# Schematic_Rev3.net
KiCad netlist of a schematic drawn in Altium Designer
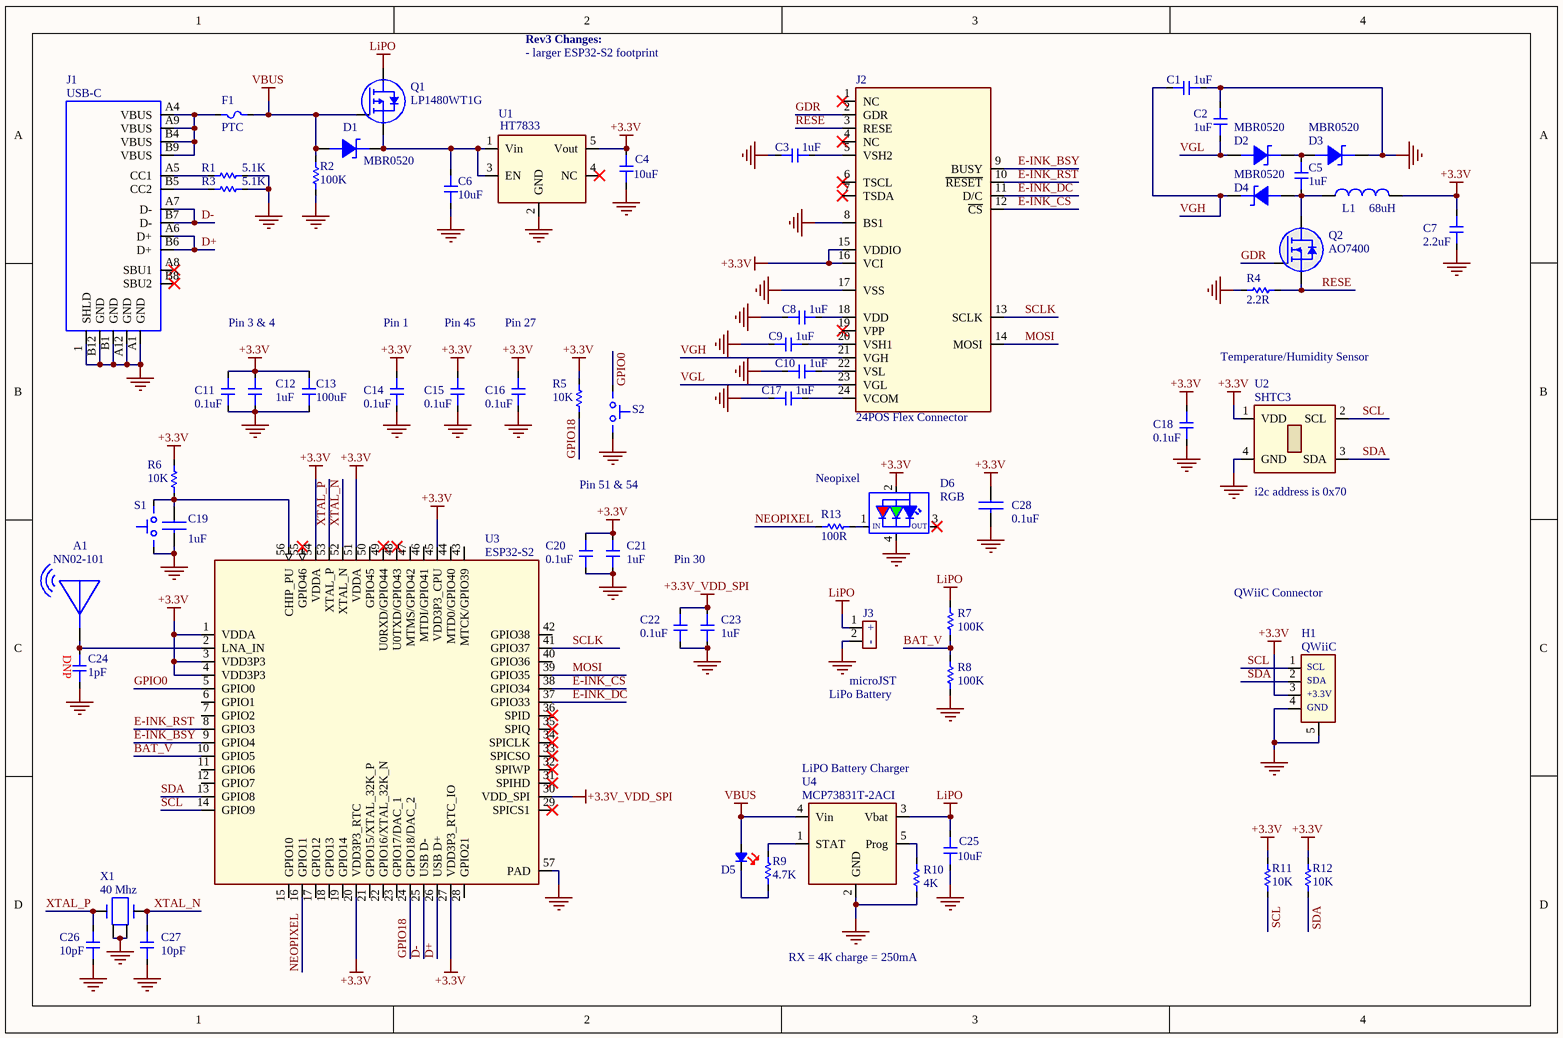
[diagram p0: Schematic_Rev3.SchDoc]

(export (version "E")
  (design (tool "Eeschema 10.0.6"))
  (components
    (comp (ref "A1")
      (value "NN02-101")
      (footprint "NN02-101")
      (description "Antenna Chip 2.4Gig")
      (fields (field (name "MANUFACTURER") "Ignion"))
      (libsource (lib "MAR") (part "NN02-101"))
    )
    (comp (ref "C1")
      (value "1uF")
      (footprint "CAPC1005X56N")
      (description "CAP 1uF 0402")
      (libsource (lib "MAR") (part "CAP_0402"))
    )
    (comp (ref "C2")
      (value "1uF")
      (footprint "CAPC1005X56N")
      (description "CAP 1uF 0402")
      (libsource (lib "MAR") (part "CAP_0402"))
    )
    (comp (ref "C3")
      (value "1uF")
      (footprint "CAPC1005X56N")
      (description "CAP 1uF 0402")
      (libsource (lib "MAR") (part "CAP_0402"))
    )
    (comp (ref "C4")
      (value "10uF")
      (footprint "CAPC2012X140N")
      (description "CAP 10uF 0805")
      (libsource (lib "MAR") (part "CAP_0805"))
    )
    (comp (ref "C5")
      (value "1uF")
      (footprint "CAPC1005X56N")
      (description "CAP 1uF 0402")
      (libsource (lib "MAR") (part "CAP_0402"))
    )
    (comp (ref "C6")
      (value "10uF")
      (footprint "CAPC2012X140N")
      (description "CAP 10uF 0805")
      (libsource (lib "MAR") (part "CAP_0805"))
    )
    (comp (ref "C7")
      (value "2.2uF")
      (footprint "CAPC1608X09L")
      (description "CAP 2.2uF 0603")
      (libsource (lib "MAR") (part "CAP_0402"))
    )
    (comp (ref "C8")
      (value "1uF")
      (footprint "CAPC1005X56N")
      (description "CAP 1uF 0402")
      (libsource (lib "MAR") (part "CAP_0402"))
    )
    (comp (ref "C9")
      (value "1uF")
      (footprint "CAPC1005X56N")
      (description "CAP 1uF 0402")
      (libsource (lib "MAR") (part "CAP_0402"))
    )
    (comp (ref "C10")
      (value "1uF")
      (footprint "CAPC1005X56N")
      (description "CAP 1uF 0402")
      (libsource (lib "MAR") (part "CAP_0402"))
    )
    (comp (ref "C11")
      (value "0.1uF")
      (footprint "CAPC1005X56N")
      (description "CAP 0.1uF 0402")
      (libsource (lib "MAR") (part "CAP_0402"))
    )
    (comp (ref "C12")
      (value "1uF")
      (footprint "CAPC1005X56N")
      (description "CAP 1uF 0402")
      (libsource (lib "MAR") (part "CAP_0402"))
    )
    (comp (ref "C13")
      (value "100uF")
      (footprint "CAPC3216X160N")
      (description "CAP 100uF 1206")
      (libsource (lib "MAR") (part "CAP_1206"))
    )
    (comp (ref "C14")
      (value "0.1uF")
      (footprint "CAPC1005X56N")
      (description "CAP 0.1uF 0402")
      (libsource (lib "MAR") (part "CAP_0402"))
    )
    (comp (ref "C15")
      (value "0.1uF")
      (footprint "CAPC1005X56N")
      (description "CAP 0.1uF 0402")
      (libsource (lib "MAR") (part "CAP_0402"))
    )
    (comp (ref "C16")
      (value "0.1uF")
      (footprint "CAPC1005X56N")
      (description "CAP 0.1uF 0402")
      (libsource (lib "MAR") (part "CAP_0402"))
    )
    (comp (ref "C17")
      (value "1uF")
      (footprint "CAPC1005X56N")
      (description "CAP 1uF 0402")
      (libsource (lib "MAR") (part "CAP_0402"))
    )
    (comp (ref "C18")
      (value "0.1uF")
      (footprint "CAPC1005X56N")
      (description "CAP 0.1uF 0402")
      (libsource (lib "MAR") (part "CAP_0402"))
    )
    (comp (ref "C19")
      (value "1uF")
      (footprint "CAPC1005X56N")
      (description "CAP 1uF 0402")
      (libsource (lib "") (part "CAP_0402_1"))
    )
    (comp (ref "C20")
      (value "0.1uF")
      (footprint "CAPC1005X56N")
      (description "CAP 0.1uF 0402")
      (libsource (lib "MAR") (part "CAP_0402"))
    )
    (comp (ref "C21")
      (value "1uF")
      (footprint "CAPC1005X56N")
      (description "CAP 1uF 0402")
      (libsource (lib "MAR") (part "CAP_0402"))
    )
    (comp (ref "C22")
      (value "0.1uF")
      (footprint "CAPC1005X56N")
      (description "CAP 0.1uF 0402")
      (libsource (lib "MAR") (part "CAP_0402"))
    )
    (comp (ref "C23")
      (value "1uF")
      (footprint "CAPC1005X56N")
      (description "CAP 0.1uF 0402")
      (libsource (lib "MAR") (part "CAP_0402"))
    )
    (comp (ref "C24")
      (value "1pF")
      (footprint "CAPC1005X56N")
      (description "CAP 1pF 0402")
      (libsource (lib "MAR") (part "CAP_0402"))
    )
    (comp (ref "C25")
      (value "10uF")
      (footprint "CAPC2012X140N")
      (description "CAP 10uF 0805")
      (libsource (lib "MAR") (part "CAP_0805"))
    )
    (comp (ref "C26")
      (value "10pF")
      (footprint "CAPC1005X56N")
      (description "CAP 10pF 0402")
      (libsource (lib "MAR") (part "CAP_0402"))
    )
    (comp (ref "C27")
      (value "10pF")
      (footprint "CAPC1005X56N")
      (description "CAP 10pF 0402")
      (libsource (lib "MAR") (part "CAP_0402"))
    )
    (comp (ref "C28")
      (value "0.1uF")
      (footprint "CAPC1005X56N")
      (description "CAP 0.1uF 0402")
      (libsource (lib "") (part "CAP_0402_1"))
    )
    (comp (ref "D1")
      (value "MBR0520")
      (footprint "SOD123")
      (description "DIODE SCHOTTKY 20V 500MA SOD-123")
      (fields (field (name "MANUFACTURER") "Micro") (field (name "PART_NUMBER") "C78746"))
      (libsource (lib "MAR") (part "MBR0520-TP"))
    )
    (comp (ref "D2")
      (value "MBR0520")
      (footprint "SOD123")
      (description "DIODE SCHOTTKY 20V 500MA SOD-123")
      (fields (field (name "MANUFACTURER") "Micro") (field (name "PART_NUMBER") "C78746"))
      (libsource (lib "MAR") (part "MBR0520-TP"))
    )
    (comp (ref "D3")
      (value "MBR0520")
      (footprint "SOD123")
      (description "DIODE SCHOTTKY 20V 500MA SOD-123")
      (fields (field (name "MANUFACTURER") "Micro") (field (name "PART_NUMBER") "C78746"))
      (libsource (lib "MAR") (part "MBR0520-TP"))
    )
    (comp (ref "D4")
      (value "MBR0520")
      (footprint "SOD123")
      (description "DIODE SCHOTTKY 20V 500MA SOD-123")
      (fields (field (name "MANUFACTURER") "Micro") (field (name "PART_NUMBER") "C78746"))
      (libsource (lib "MAR") (part "MBR0520-TP"))
    )
    (comp (ref "D5")
      (value "Red Led")
      (footprint "LED1005X40N-Red")
      (description "LED Red 0402")
      (fields (field (name "PART_NUMBER") "C364556") (field (name "MANUFACTURER") "Lite-On"))
      (libsource (lib "MAR") (part "LED_0402_SMALL_Red"))
    )
    (comp (ref "D6")
      (value "RGB")
      (footprint "SK6805-E-J")
      (description "LED,RGB,NEOPIXEL,SK6805-E-J 1515")
      (fields (field (name "PART_NUMBER") "4492") (field (name "MANUFACTURER") "Adafruit"))
      (libsource (lib "MAR") (part "SK6805-E-J-1515"))
    )
    (comp (ref "F1")
      (value "TLC-PSMD050")
      (footprint "RESC1608X06L (0603 FOOTPRINT)")
      (description "PTC FUSE 500mA hold, 1A trip")
      (fields (field (name "MANUFACTURER") "TLC") (field (name "PART_NUMBER") "C261942"))
      (libsource (lib "MAR") (part "PTC_FUSE"))
    )
    (comp (ref "H1")
      (value "QWiiC")
      (footprint "SM04B-SRSS-TB")
      (description "CONN HEADER 4POS .100 R/A QWIIC")
      (fields (field (name "MANUFACTURER") "JST") (field (name "PART_NUMBER") "PRT-14417"))
      (libsource (lib "MAR") (part "SM04B-SRSS-TB"))
    )
    (comp (ref "J1")
      (value "USB-C")
      (footprint "TYPE-C-31-M-12")
      (description "CONN RECPT USB-C")
      (fields (field (name "MANUFACTURER") "KHE") (field (name "PART_NUMBER") "C165948"))
      (libsource (lib "MAR") (part "USB-C"))
    )
    (comp (ref "J2")
      (value "24POS Flex Connector")
      (footprint "687124182122")
      (description "CONN FFC TOP/BOT 24POS 0.50MM R/A")
      (fields (field (name "MANUFACTURER") "Wurth") (field (name "PART_NUMBER") "687124182122"))
      (libsource (lib "MAR") (part "687124182122"))
    )
    (comp (ref "J3")
      (value "CON2")
      (footprint "JST_Micro_2PIN")
      (description "JST MIcro CONN 2POS")
      (libsource (lib "MAR") (part "JST_Micro_CONN_2PIN"))
    )
    (comp (ref "L1")
      (value "68uH")
      (footprint "INDUCTOR, 3mmX3mm")
      (description "INDUCTOR 68uH 20% 4mmx4mm")
      (fields (field (name "PART_NUMBER") "C135265") (field (name "MANUFACTURER") "SXN"))
      (libsource (lib "MAR") (part "68uH"))
    )
    (comp (ref "Q1")
      (value "LP1480WT1G")
      (footprint "SC-70")
      (description "MOSFET P-CH 20V 1.4A SC-70")
      (fields (field (name "MANUFACTURER") "LRC") (field (name "PART_NUMBER") "C172434"))
      (libsource (lib "MAR") (part "LP1480WT1G"))
    )
    (comp (ref "Q2")
      (value "AO7400")
      (footprint "SC-70")
      (description "MOSFET N-CH 20V 4A SC70-3")
      (fields (field (name "MANUFACTURER") "VBSemi Elec"))
      (libsource (lib "MAR") (part "AO7400"))
    )
    (comp (ref "R1")
      (value "5.1K")
      (footprint "RESC1005X40L (0402 FOOTPRINT)")
      (description "RES 5.1K 0402")
      (libsource (lib "MAR") (part "RES_0402"))
    )
    (comp (ref "R2")
      (value "100K")
      (footprint "RESC1005X40L (0402 FOOTPRINT)")
      (description "RES 100K 0402")
      (libsource (lib "MAR") (part "RES_0402"))
    )
    (comp (ref "R3")
      (value "5.1K")
      (footprint "RESC1005X40L (0402 FOOTPRINT)")
      (description "RES 5.1K 0402")
      (libsource (lib "MAR") (part "RES_0402"))
    )
    (comp (ref "R4")
      (value "2.2R")
      (footprint "RESC1005X40L (0402 FOOTPRINT)")
      (description "RES 2.2R 0402")
      (libsource (lib "MAR") (part "RES_0402"))
    )
    (comp (ref "R5")
      (value "10K")
      (footprint "RESC1005X40L (0402 FOOTPRINT)")
      (description "RES 10K 0402")
      (fields (field (name "LCSC_PART_NUMBER") "C258091") (field (name "MANUFACTURER") "Guangdong"))
      (libsource (lib "MAR") (part "RES_0402"))
    )
    (comp (ref "R6")
      (value "10K")
      (footprint "RESC1005X40L (0402 FOOTPRINT)")
      (description "RES 10K 0402")
      (fields (field (name "LCSC_PART_NUMBER") "C258091") (field (name "MANUFACTURER") "Guangdong"))
      (libsource (lib "MAR") (part "RES_0402"))
    )
    (comp (ref "R7")
      (value "100K")
      (footprint "RESC1005X40L (0402 FOOTPRINT)")
      (description "RES 100K 0402")
      (libsource (lib "MAR") (part "RES_0402"))
    )
    (comp (ref "R8")
      (value "100K")
      (footprint "RESC1005X40L (0402 FOOTPRINT)")
      (description "RES 100K 0402")
      (libsource (lib "MAR") (part "RES_0402"))
    )
    (comp (ref "R9")
      (value "4.7K")
      (footprint "RESC1005X40L (0402 FOOTPRINT)")
      (description "RES 4.7K 0402")
      (libsource (lib "MAR") (part "RES_0402"))
    )
    (comp (ref "R10")
      (value "4K")
      (footprint "RESC1005X40L (0402 FOOTPRINT)")
      (description "RES 4K 0402")
      (libsource (lib "MAR") (part "RES_0402"))
    )
    (comp (ref "R11")
      (value "10K")
      (footprint "RESC1005X40L (0402 FOOTPRINT)")
      (description "RES 10K 0402")
      (libsource (lib "MAR") (part "RES_0402"))
    )
    (comp (ref "R12")
      (value "10K")
      (footprint "RESC1005X40L (0402 FOOTPRINT)")
      (description "RES 10K 0402")
      (libsource (lib "MAR") (part "RES_0402"))
    )
    (comp (ref "R13")
      (value "100R")
      (footprint "RESC1005X40L (0402 FOOTPRINT)")
      (description "RES 100R 0402")
      (fields (field (name "MANUFACTURER") "Yageo") (field (name "PARTNUMBER") "C106232"))
      (libsource (lib "MAR") (part "RES_0603"))
    )
    (comp (ref "S1")
      (value "~")
      (footprint "TS-1088R-02526")
      (description "Tactile Micro Switch")
      (fields (field (name "PART_NUMBER") "C455281") (field (name "MANUFACTURER") "XUNPU"))
      (libsource (lib "MAR") (part "TS-1088R-02526"))
    )
    (comp (ref "S2")
      (value "~")
      (footprint "TS-1088R-02526")
      (description "Tactile Micro Switch")
      (fields (field (name "PART_NUMBER") "C455281") (field (name "MANUFACTURER") "XUNPU"))
      (libsource (lib "MAR") (part "TS-1088R-02526"))
    )
    (comp (ref "U1")
      (value "HT7833")
      (footprint "SOT95P280X144-5N")
      (description "IC LDO 3.3V 0.5A SOT23-5")
      (fields (field (name "MANUFACTURER") "Holtek") (field (name "PART_NUMBER") "C164106"))
      (libsource (lib "MAR") (part "HT7833"))
    )
    (comp (ref "U2")
      (value "SHTC3")
      (footprint "DFN-4 (2.0mm X 2.0mm)")
      (description "Humidity/Temperature Sensor")
      (fields (field (name "MANUFACTURER") "Sensirion") (field (name "PART_NUMBER") "SHTC3"))
      (libsource (lib "MAR") (part "SHTC3"))
    )
    (comp (ref "U3")
      (value "ESP32-S2")
      (footprint "QFN56_0.4mm pitch - Rev2")
      (description "WIFI/Bluetooth, w/ 4M Flash, 2M PSRAM, QFN-56 7x7")
      (fields (field (name "MANUFACTURER") "Espressif") (field (name "PART_NUMBER") "ESP32-S2FN4R2"))
      (libsource (lib "MAR") (part "ESP32-S2"))
    )
    (comp (ref "U4")
      (value "MCP73831T-2ACI")
      (footprint "SOT95P280X144-5N")
      (description "Charger IC Lithium-Ion/Polymer SOT23-5")
      (fields (field (name "MANUFACTURER") "Microchip") (field (name "PART_NUMBER") "MCP73831T-2ACI/OT"))
      (libsource (lib "MAR") (part "MCP73831T-2ACI/OT"))
    )
    (comp (ref "X1")
      (value "40 Mhz")
      (footprint "OSC20X16")
      (description "CRYSTAL 40MHZ 10PF SMD")
      (fields (field (name "PART_NUMBER") "ECS-400-10-37B2-CKM") (field (name "MANUFACTURER") "ECS"))
      (libsource (lib "MAR") (part "40Mhz"))
    )
  )
  (nets
    (net (code "1") (name "+3.3V") (class "Default")
      (node (ref "C11") (pin "1") (pintype "passive"))
      (node (ref "C12") (pin "1") (pintype "passive"))
      (node (ref "C13") (pin "1") (pintype "passive"))
      (node (ref "C14") (pin "1") (pintype "passive"))
      (node (ref "C15") (pin "1") (pintype "passive"))
      (node (ref "C16") (pin "1") (pintype "passive"))
      (node (ref "C18") (pin "1") (pintype "passive"))
      (node (ref "C20") (pin "1") (pintype "passive"))
      (node (ref "C21") (pin "1") (pintype "passive"))
      (node (ref "C28") (pin "1") (pinfunction "1_1") (pintype "passive"))
      (node (ref "C4") (pin "1") (pintype "passive"))
      (node (ref "C7") (pin "1") (pintype "passive"))
      (node (ref "D6") (pin "2") (pinfunction "VDD_2") (pintype "passive"))
      (node (ref "H1") (pin "3") (pintype "passive"))
      (node (ref "J2") (pin "15") (pinfunction "VDDIO_15") (pintype "power_in"))
      (node (ref "J2") (pin "16") (pinfunction "VCI_16") (pintype "power_in"))
      (node (ref "L1") (pin "2") (pinfunction "2_2") (pintype "passive"))
      (node (ref "R11") (pin "2") (pintype "passive"))
      (node (ref "R12") (pin "2") (pintype "passive"))
      (node (ref "R5") (pin "1") (pintype "passive"))
      (node (ref "R6") (pin "1") (pintype "passive"))
      (node (ref "U1") (pin "5") (pinfunction "Vout_5") (pintype "passive"))
      (node (ref "U2") (pin "1") (pinfunction "VDD_1") (pintype "power_in"))
      (node (ref "U3") (pin "1") (pinfunction "VDDA_1") (pintype "power_in"))
      (node (ref "U3") (pin "20") (pinfunction "VDD3P3_RTC_20") (pintype "power_in"))
      (node (ref "U3") (pin "27") (pinfunction "VDD3P3_RTC_IO_27") (pintype "power_in"))
      (node (ref "U3") (pin "3") (pinfunction "VDD3P3_3") (pintype "power_in"))
      (node (ref "U3") (pin "4") (pinfunction "VDD3P3_4") (pintype "power_in"))
      (node (ref "U3") (pin "45") (pinfunction "VDD3P3_CPU_45") (pintype "power_in"))
      (node (ref "U3") (pin "51") (pinfunction "VDDA_51") (pintype "power_in"))
      (node (ref "U3") (pin "54") (pinfunction "VDDA_54") (pintype "power_in"))
    )
    (net (code "2") (name "+3.3V_VDD_SPI") (class "Default")
      (node (ref "C22") (pin "1") (pintype "passive"))
      (node (ref "C23") (pin "1") (pintype "passive"))
      (node (ref "U3") (pin "30") (pinfunction "VDD_SPI_30") (pintype "power_in"))
    )
    (net (code "3") (name "/BAT_V") (class "Default")
      (node (ref "R7") (pin "1") (pintype "passive"))
      (node (ref "R8") (pin "2") (pintype "passive"))
      (node (ref "U3") (pin "10") (pinfunction "GPIO5_10") (pintype "passive"))
    )
    (net (code "4") (name "/D+") (class "Default")
      (node (ref "J1") (pin "A6") (pinfunction "D+_A6") (pintype "power_in"))
      (node (ref "J1") (pin "B6") (pinfunction "D+_B6") (pintype "power_in"))
      (node (ref "U3") (pin "26") (pinfunction "USB_D+_26") (pintype "passive"))
    )
    (net (code "5") (name "/D-") (class "Default")
      (node (ref "J1") (pin "A7") (pinfunction "D-_A7") (pintype "power_in"))
      (node (ref "J1") (pin "B7") (pinfunction "D-_B7") (pintype "power_in"))
      (node (ref "U3") (pin "25") (pinfunction "USB_D-_25") (pintype "passive"))
    )
    (net (code "6") (name "/E-INK_BSY") (class "Default")
      (node (ref "J2") (pin "9") (pinfunction "BUSY_9") (pintype "passive"))
      (node (ref "U3") (pin "9") (pinfunction "GPIO4_9") (pintype "passive"))
    )
    (net (code "7") (name "/E-INK_CS") (class "Default")
      (node (ref "J2") (pin "12") (pinfunction "~{CS}_12") (pintype "passive"))
      (node (ref "U3") (pin "38") (pinfunction "GPIO34_38") (pintype "passive"))
    )
    (net (code "8") (name "/E-INK_DC") (class "Default")
      (node (ref "J2") (pin "11") (pinfunction "D/C_11") (pintype "passive"))
      (node (ref "U3") (pin "37") (pinfunction "GPIO33_37") (pintype "passive"))
    )
    (net (code "9") (name "/E-INK_RST") (class "Default")
      (node (ref "J2") (pin "10") (pinfunction "~{RESET}_10") (pintype "passive"))
      (node (ref "U3") (pin "8") (pinfunction "GPIO3_8") (pintype "passive"))
    )
    (net (code "10") (name "/GDR") (class "Default")
      (node (ref "J2") (pin "2") (pinfunction "GDR_2") (pintype "passive"))
      (node (ref "Q2") (pin "1") (pinfunction "G_1") (pintype "passive"))
    )
    (net (code "11") (name "/GPIO0") (class "Default")
      (node (ref "S2") (pin "1") (pinfunction "A_1") (pintype "passive"))
      (node (ref "U3") (pin "5") (pinfunction "GPIO0_5") (pintype "passive"))
    )
    (net (code "12") (name "/GPIO18") (class "Default")
      (node (ref "R5") (pin "2") (pintype "passive"))
      (node (ref "U3") (pin "24") (pinfunction "GPIO18/DAC_2_24") (pintype "passive"))
    )
    (net (code "13") (name "/MOSI") (class "Default")
      (node (ref "J2") (pin "14") (pinfunction "MOSI_14") (pintype "passive"))
      (node (ref "U3") (pin "39") (pinfunction "GPIO35_39") (pintype "passive"))
    )
    (net (code "14") (name "/NEOPIXEL") (class "Default")
      (node (ref "R13") (pin "2") (pintype "passive"))
      (node (ref "U3") (pin "16") (pinfunction "GPIO11_16") (pintype "passive"))
    )
    (net (code "15") (name "/RESE") (class "Default")
      (node (ref "J2") (pin "3") (pinfunction "RESE_3") (pintype "passive"))
      (node (ref "Q2") (pin "2") (pinfunction "S_2") (pintype "passive"))
      (node (ref "R4") (pin "1") (pintype "passive"))
    )
    (net (code "16") (name "/SCL") (class "Default")
      (node (ref "H1") (pin "1") (pintype "passive"))
      (node (ref "R11") (pin "1") (pintype "passive"))
      (node (ref "U2") (pin "2") (pinfunction "SCL_2") (pintype "passive"))
      (node (ref "U3") (pin "14") (pinfunction "GPIO9_14") (pintype "passive"))
    )
    (net (code "17") (name "/SCLK") (class "Default")
      (node (ref "J2") (pin "13") (pinfunction "SCLK_13") (pintype "passive"))
      (node (ref "U3") (pin "41") (pinfunction "GPIO37_41") (pintype "passive"))
    )
    (net (code "18") (name "/SDA") (class "Default")
      (node (ref "H1") (pin "2") (pintype "passive"))
      (node (ref "R12") (pin "1") (pintype "passive"))
      (node (ref "U2") (pin "3") (pinfunction "SDA_3") (pintype "passive"))
      (node (ref "U3") (pin "13") (pinfunction "GPIO8_13") (pintype "passive"))
    )
    (net (code "19") (name "/VGH") (class "Default")
      (node (ref "C1") (pin "1") (pintype "passive"))
      (node (ref "D4") (pin "1") (pinfunction "Cathode_1") (pintype "passive"))
      (node (ref "J2") (pin "21") (pinfunction "VGH_21") (pintype "passive"))
    )
    (net (code "20") (name "/VGL") (class "Default")
      (node (ref "C2") (pin "2") (pintype "passive"))
      (node (ref "D2") (pin "2") (pinfunction "Annode_2") (pintype "passive"))
      (node (ref "J2") (pin "23") (pinfunction "VGL_23") (pintype "passive"))
    )
    (net (code "21") (name "/XTAL_N") (class "Default")
      (node (ref "C27") (pin "1") (pintype "passive"))
      (node (ref "U3") (pin "52") (pinfunction "XTAL_N_52") (pintype "passive"))
      (node (ref "X1") (pin "3") (pinfunction "3_3") (pintype "passive"))
    )
    (net (code "22") (name "/XTAL_P") (class "Default")
      (node (ref "C26") (pin "1") (pintype "passive"))
      (node (ref "U3") (pin "53") (pinfunction "XTAL_P_53") (pintype "passive"))
      (node (ref "X1") (pin "1") (pinfunction "1_1") (pintype "passive"))
    )
    (net (code "23") (name "GND") (class "Default")
      (node (ref "C1") (pin "2") (pintype "passive"))
      (node (ref "C10") (pin "1") (pintype "passive"))
      (node (ref "C11") (pin "2") (pintype "passive"))
      (node (ref "C12") (pin "2") (pintype "passive"))
      (node (ref "C13") (pin "2") (pintype "passive"))
      (node (ref "C14") (pin "2") (pintype "passive"))
      (node (ref "C15") (pin "2") (pintype "passive"))
      (node (ref "C16") (pin "2") (pintype "passive"))
      (node (ref "C17") (pin "1") (pintype "passive"))
      (node (ref "C18") (pin "2") (pintype "passive"))
      (node (ref "C19") (pin "2") (pinfunction "2_2") (pintype "passive"))
      (node (ref "C2") (pin "1") (pintype "passive"))
      (node (ref "C20") (pin "2") (pintype "passive"))
      (node (ref "C21") (pin "2") (pintype "passive"))
      (node (ref "C22") (pin "2") (pintype "passive"))
      (node (ref "C23") (pin "2") (pintype "passive"))
      (node (ref "C24") (pin "2") (pintype "passive"))
      (node (ref "C25") (pin "2") (pintype "passive"))
      (node (ref "C26") (pin "2") (pintype "passive"))
      (node (ref "C27") (pin "2") (pintype "passive"))
      (node (ref "C28") (pin "2") (pinfunction "2_2") (pintype "passive"))
      (node (ref "C3") (pin "1") (pintype "passive"))
      (node (ref "C4") (pin "2") (pintype "passive"))
      (node (ref "C6") (pin "2") (pintype "passive"))
      (node (ref "C7") (pin "2") (pintype "passive"))
      (node (ref "C8") (pin "1") (pintype "passive"))
      (node (ref "C9") (pin "1") (pintype "passive"))
      (node (ref "D3") (pin "1") (pinfunction "Cathode_1") (pintype "passive"))
      (node (ref "D6") (pin "4") (pinfunction "GND_4") (pintype "passive"))
      (node (ref "H1") (pin "4") (pintype "passive"))
      (node (ref "H1") (pin "5") (pintype "passive"))
      (node (ref "J1") (pin "1") (pinfunction "SHLD_1") (pintype "power_in"))
      (node (ref "J1") (pin "A1") (pinfunction "GND_A1") (pintype "power_in"))
      (node (ref "J1") (pin "A12") (pinfunction "GND_A12") (pintype "power_in"))
      (node (ref "J1") (pin "B1") (pinfunction "GND_B1") (pintype "power_in"))
      (node (ref "J1") (pin "B12") (pinfunction "GND_B12") (pintype "passive"))
      (node (ref "J2") (pin "17") (pinfunction "VSS_17") (pintype "power_in"))
      (node (ref "J2") (pin "8") (pinfunction "BS1_8") (pintype "passive"))
      (node (ref "J3") (pin "2") (pintype "passive"))
      (node (ref "R1") (pin "1") (pintype "passive"))
      (node (ref "R10") (pin "1") (pintype "passive"))
      (node (ref "R2") (pin "2") (pintype "passive"))
      (node (ref "R3") (pin "1") (pintype "passive"))
      (node (ref "R4") (pin "2") (pintype "passive"))
      (node (ref "R8") (pin "1") (pintype "passive"))
      (node (ref "S1") (pin "2") (pinfunction "B_2") (pintype "passive"))
      (node (ref "S2") (pin "2") (pinfunction "B_2") (pintype "passive"))
      (node (ref "U1") (pin "2") (pinfunction "GND_2") (pintype "power_in"))
      (node (ref "U2") (pin "4") (pinfunction "GND_4") (pintype "power_in"))
      (node (ref "U3") (pin "57") (pinfunction "PAD_57") (pintype "power_in"))
      (node (ref "U4") (pin "2") (pinfunction "GND_2") (pintype "power_in"))
      (node (ref "X1") (pin "2") (pinfunction "2_2") (pintype "power_in"))
      (node (ref "X1") (pin "4") (pinfunction "4_4") (pintype "power_in"))
    )
    (net (code "24") (name "LiPO") (class "Default")
      (node (ref "C25") (pin "1") (pintype "passive"))
      (node (ref "J3") (pin "1") (pintype "passive"))
      (node (ref "Q1") (pin "3") (pinfunction "D_3") (pintype "passive"))
      (node (ref "R7") (pin "2") (pintype "passive"))
      (node (ref "U4") (pin "3") (pinfunction "Vbat_3") (pintype "passive"))
    )
    (net (code "25") (name "Net-(D1-Cathode)") (class "Default")
      (node (ref "C6") (pin "1") (pintype "passive"))
      (node (ref "D1") (pin "1") (pinfunction "Cathode_1") (pintype "passive"))
      (node (ref "Q1") (pin "2") (pinfunction "S_2") (pintype "passive"))
      (node (ref "U1") (pin "1") (pinfunction "Vin_1") (pintype "passive"))
      (node (ref "U1") (pin "3") (pinfunction "EN_3") (pintype "passive"))
    )
    (net (code "26") (name "Net-(D2-Cathode)") (class "Default")
      (node (ref "C5") (pin "1") (pintype "passive"))
      (node (ref "D2") (pin "1") (pinfunction "Cathode_1") (pintype "passive"))
      (node (ref "D3") (pin "2") (pinfunction "Annode_2") (pintype "passive"))
    )
    (net (code "27") (name "Net-(D4-Annode)") (class "Default")
      (node (ref "C5") (pin "2") (pintype "passive"))
      (node (ref "D4") (pin "2") (pinfunction "Annode_2") (pintype "passive"))
      (node (ref "L1") (pin "1") (pinfunction "1_1") (pintype "passive"))
      (node (ref "Q2") (pin "3") (pinfunction "D_3") (pintype "passive"))
    )
    (net (code "28") (name "Net-(D5-Pad1)") (class "Default")
      (node (ref "D5") (pin "1") (pintype "passive"))
      (node (ref "R9") (pin "1") (pintype "passive"))
    )
    (net (code "29") (name "Net-(D6-DIN)") (class "Default")
      (node (ref "D6") (pin "1") (pinfunction "DIN_1") (pintype "passive"))
      (node (ref "R13") (pin "1") (pintype "passive"))
    )
    (net (code "30") (name "Net-(F1-Pad2)") (class "Default")
      (node (ref "F1") (pin "2") (pintype "passive"))
      (node (ref "J1") (pin "A4") (pinfunction "VBUS_A4") (pintype "passive"))
      (node (ref "J1") (pin "A9") (pinfunction "VBUS_A9") (pintype "power_in"))
      (node (ref "J1") (pin "B4") (pinfunction "VBUS_B4") (pintype "power_in"))
      (node (ref "J1") (pin "B9") (pinfunction "VBUS_B9") (pintype "passive"))
    )
    (net (code "31") (name "Net-(J1-CC1)") (class "Default")
      (node (ref "J1") (pin "A5") (pinfunction "CC1_A5") (pintype "power_in"))
      (node (ref "R1") (pin "2") (pintype "passive"))
    )
    (net (code "32") (name "Net-(J1-CC2)") (class "Default")
      (node (ref "J1") (pin "B5") (pinfunction "CC2_B5") (pintype "power_in"))
      (node (ref "R3") (pin "2") (pintype "passive"))
    )
    (net (code "33") (name "Net-(J2-VCOM)") (class "Default")
      (node (ref "C17") (pin "2") (pintype "passive"))
      (node (ref "J2") (pin "24") (pinfunction "VCOM_24") (pintype "passive"))
    )
    (net (code "34") (name "Net-(J2-VDD)") (class "Default")
      (node (ref "C8") (pin "2") (pintype "passive"))
      (node (ref "J2") (pin "18") (pinfunction "VDD_18") (pintype "power_in"))
    )
    (net (code "35") (name "Net-(J2-VSH1)") (class "Default")
      (node (ref "C9") (pin "2") (pintype "passive"))
      (node (ref "J2") (pin "20") (pinfunction "VSH1_20") (pintype "passive"))
    )
    (net (code "36") (name "Net-(J2-VSH2)") (class "Default")
      (node (ref "C3") (pin "2") (pintype "passive"))
      (node (ref "J2") (pin "5") (pinfunction "VSH2_5") (pintype "passive"))
    )
    (net (code "37") (name "Net-(J2-VSL)") (class "Default")
      (node (ref "C10") (pin "2") (pintype "passive"))
      (node (ref "J2") (pin "22") (pinfunction "VSL_22") (pintype "passive"))
    )
    (net (code "38") (name "Net-(S1-A)") (class "Default")
      (node (ref "C19") (pin "1") (pinfunction "1_1") (pintype "passive"))
      (node (ref "R6") (pin "2") (pintype "passive"))
      (node (ref "S1") (pin "1") (pinfunction "A_1") (pintype "passive"))
      (node (ref "U3") (pin "56") (pinfunction "CHIP_PU_56") (pintype "input"))
    )
    (net (code "39") (name "Net-(U3-LNA_IN)") (class "Default")
      (node (ref "A1") (pin "1") (pintype "passive"))
      (node (ref "C24") (pin "1") (pintype "passive"))
      (node (ref "U3") (pin "2") (pinfunction "LNA_IN_2") (pintype "passive"))
    )
    (net (code "40") (name "Net-(U4-Prog)") (class "Default")
      (node (ref "R10") (pin "2") (pintype "passive"))
      (node (ref "U4") (pin "5") (pinfunction "Prog_5") (pintype "passive"))
    )
    (net (code "41") (name "Net-(U4-STAT)") (class "Default")
      (node (ref "R9") (pin "2") (pintype "passive"))
      (node (ref "U4") (pin "1") (pinfunction "STAT_1") (pintype "passive"))
    )
    (net (code "42") (name "VBUS") (class "Default")
      (node (ref "D1") (pin "2") (pinfunction "Annode_2") (pintype "passive"))
      (node (ref "D5") (pin "2") (pintype "passive"))
      (node (ref "F1") (pin "1") (pintype "passive"))
      (node (ref "Q1") (pin "1") (pinfunction "G_1") (pintype "passive"))
      (node (ref "R2") (pin "1") (pintype "passive"))
      (node (ref "U4") (pin "4") (pinfunction "Vin_4") (pintype "passive"))
    )
    (net (code "43") (name "unconnected-(D6-DOUT-Pad3)") (class "Default")
      (node (ref "D6") (pin "3") (pinfunction "DOUT_3") (pintype "passive+no_connect"))
    )
    (net (code "44") (name "unconnected-(J1-SBU1-PadA8)") (class "Default")
      (node (ref "J1") (pin "A8") (pinfunction "SBU1_A8") (pintype "power_in+no_connect"))
    )
    (net (code "45") (name "unconnected-(J1-SBU2-PadB8)") (class "Default")
      (node (ref "J1") (pin "B8") (pinfunction "SBU2_B8") (pintype "power_in+no_connect"))
    )
    (net (code "46") (name "unconnected-(J2-NC-Pad1)") (class "Default")
      (node (ref "J2") (pin "1") (pinfunction "NC_1") (pintype "passive+no_connect"))
    )
    (net (code "47") (name "unconnected-(J2-NC-Pad4)") (class "Default")
      (node (ref "J2") (pin "4") (pinfunction "NC_4") (pintype "passive+no_connect"))
    )
    (net (code "48") (name "unconnected-(J2-TSCL-Pad6)") (class "Default")
      (node (ref "J2") (pin "6") (pinfunction "TSCL_6") (pintype "passive+no_connect"))
    )
    (net (code "49") (name "unconnected-(J2-TSDA-Pad7)") (class "Default")
      (node (ref "J2") (pin "7") (pinfunction "TSDA_7") (pintype "passive+no_connect"))
    )
    (net (code "50") (name "unconnected-(J2-VPP-Pad19)") (class "Default")
      (node (ref "J2") (pin "19") (pinfunction "VPP_19") (pintype "passive+no_connect"))
    )
    (net (code "51") (name "unconnected-(U1-NC-Pad4)") (class "Default")
      (node (ref "U1") (pin "4") (pinfunction "NC_4") (pintype "passive+no_connect"))
    )
    (net (code "52") (name "unconnected-(U3-GPIO1-Pad6)") (class "Default")
      (node (ref "U3") (pin "6") (pinfunction "GPIO1_6") (pintype "passive"))
    )
    (net (code "53") (name "unconnected-(U3-GPIO2-Pad7)") (class "Default")
      (node (ref "U3") (pin "7") (pinfunction "GPIO2_7") (pintype "passive"))
    )
    (net (code "54") (name "unconnected-(U3-GPIO6-Pad11)") (class "Default")
      (node (ref "U3") (pin "11") (pinfunction "GPIO6_11") (pintype "passive"))
    )
    (net (code "55") (name "unconnected-(U3-GPIO7-Pad12)") (class "Default")
      (node (ref "U3") (pin "12") (pinfunction "GPIO7_12") (pintype "passive"))
    )
    (net (code "56") (name "unconnected-(U3-GPIO10-Pad15)") (class "Default")
      (node (ref "U3") (pin "15") (pinfunction "GPIO10_15") (pintype "passive"))
    )
    (net (code "57") (name "unconnected-(U3-GPIO12-Pad17)") (class "Default")
      (node (ref "U3") (pin "17") (pinfunction "GPIO12_17") (pintype "passive"))
    )
    (net (code "58") (name "unconnected-(U3-GPIO13-Pad18)") (class "Default")
      (node (ref "U3") (pin "18") (pinfunction "GPIO13_18") (pintype "passive"))
    )
    (net (code "59") (name "unconnected-(U3-GPIO14-Pad19)") (class "Default")
      (node (ref "U3") (pin "19") (pinfunction "GPIO14_19") (pintype "passive"))
    )
    (net (code "60") (name "unconnected-(U3-GPIO15{slash}XTAL_32K_P-Pad21)") (class "Default")
      (node (ref "U3") (pin "21") (pinfunction "GPIO15/XTAL_32K_P_21") (pintype "passive"))
    )
    (net (code "61") (name "unconnected-(U3-GPIO16{slash}XTAL_32K_N-Pad22)") (class "Default")
      (node (ref "U3") (pin "22") (pinfunction "GPIO16/XTAL_32K_N_22") (pintype "passive"))
    )
    (net (code "62") (name "unconnected-(U3-GPIO17{slash}DAC_1-Pad23)") (class "Default")
      (node (ref "U3") (pin "23") (pinfunction "GPIO17/DAC_1_23") (pintype "passive"))
    )
    (net (code "63") (name "unconnected-(U3-GPIO21-Pad28)") (class "Default")
      (node (ref "U3") (pin "28") (pinfunction "GPIO21_28") (pintype "passive"))
    )
    (net (code "64") (name "unconnected-(U3-GPIO36-Pad40)") (class "Default")
      (node (ref "U3") (pin "40") (pinfunction "GPIO36_40") (pintype "passive"))
    )
    (net (code "65") (name "unconnected-(U3-GPIO38-Pad42)") (class "Default")
      (node (ref "U3") (pin "42") (pinfunction "GPIO38_42") (pintype "passive"))
    )
    (net (code "66") (name "unconnected-(U3-GPIO45-Pad50)") (class "Default")
      (node (ref "U3") (pin "50") (pinfunction "GPIO45_50") (pintype "passive"))
    )
    (net (code "67") (name "unconnected-(U3-GPIO46-Pad55)") (class "Default")
      (node (ref "U3") (pin "55") (pinfunction "GPIO46_55") (pintype "input+no_connect"))
    )
    (net (code "68") (name "unconnected-(U3-MTCK{slash}GPIO39-Pad43)") (class "Default")
      (node (ref "U3") (pin "43") (pinfunction "MTCK/GPIO39_43") (pintype "passive"))
    )
    (net (code "69") (name "unconnected-(U3-MTD0{slash}GPIO40-Pad44)") (class "Default")
      (node (ref "U3") (pin "44") (pinfunction "MTD0/GPIO40_44") (pintype "passive"))
    )
    (net (code "70") (name "unconnected-(U3-MTDI{slash}GPIO41-Pad46)") (class "Default")
      (node (ref "U3") (pin "46") (pinfunction "MTDI/GPIO41_46") (pintype "passive"))
    )
    (net (code "71") (name "unconnected-(U3-MTMS{slash}GPIO42-Pad47)") (class "Default")
      (node (ref "U3") (pin "47") (pinfunction "MTMS/GPIO42_47") (pintype "passive"))
    )
    (net (code "72") (name "unconnected-(U3-SPICLK-Pad34)") (class "Default")
      (node (ref "U3") (pin "34") (pinfunction "SPICLK_34") (pintype "passive+no_connect"))
    )
    (net (code "73") (name "unconnected-(U3-SPICS1-Pad29)") (class "Default")
      (node (ref "U3") (pin "29") (pinfunction "SPICS1_29") (pintype "passive+no_connect"))
    )
    (net (code "74") (name "unconnected-(U3-SPICSO-Pad33)") (class "Default")
      (node (ref "U3") (pin "33") (pinfunction "SPICSO_33") (pintype "passive+no_connect"))
    )
    (net (code "75") (name "unconnected-(U3-SPID-Pad36)") (class "Default")
      (node (ref "U3") (pin "36") (pinfunction "SPID_36") (pintype "passive+no_connect"))
    )
    (net (code "76") (name "unconnected-(U3-SPIHD-Pad31)") (class "Default")
      (node (ref "U3") (pin "31") (pinfunction "SPIHD_31") (pintype "passive+no_connect"))
    )
    (net (code "77") (name "unconnected-(U3-SPIQ-Pad35)") (class "Default")
      (node (ref "U3") (pin "35") (pinfunction "SPIQ_35") (pintype "passive+no_connect"))
    )
    (net (code "78") (name "unconnected-(U3-SPIWP-Pad32)") (class "Default")
      (node (ref "U3") (pin "32") (pinfunction "SPIWP_32") (pintype "passive+no_connect"))
    )
    (net (code "79") (name "unconnected-(U3-U0RXD{slash}GPIO44-Pad49)") (class "Default")
      (node (ref "U3") (pin "49") (pinfunction "U0RXD/GPIO44_49") (pintype "passive+no_connect"))
    )
    (net (code "80") (name "unconnected-(U3-U0TXD{slash}GPIO43-Pad48)") (class "Default")
      (node (ref "U3") (pin "48") (pinfunction "U0TXD/GPIO43_48") (pintype "passive+no_connect"))
    )
  )
)
